# PrimaryLogger.net
KiCad netlist of a schematic drawn in EAGLE
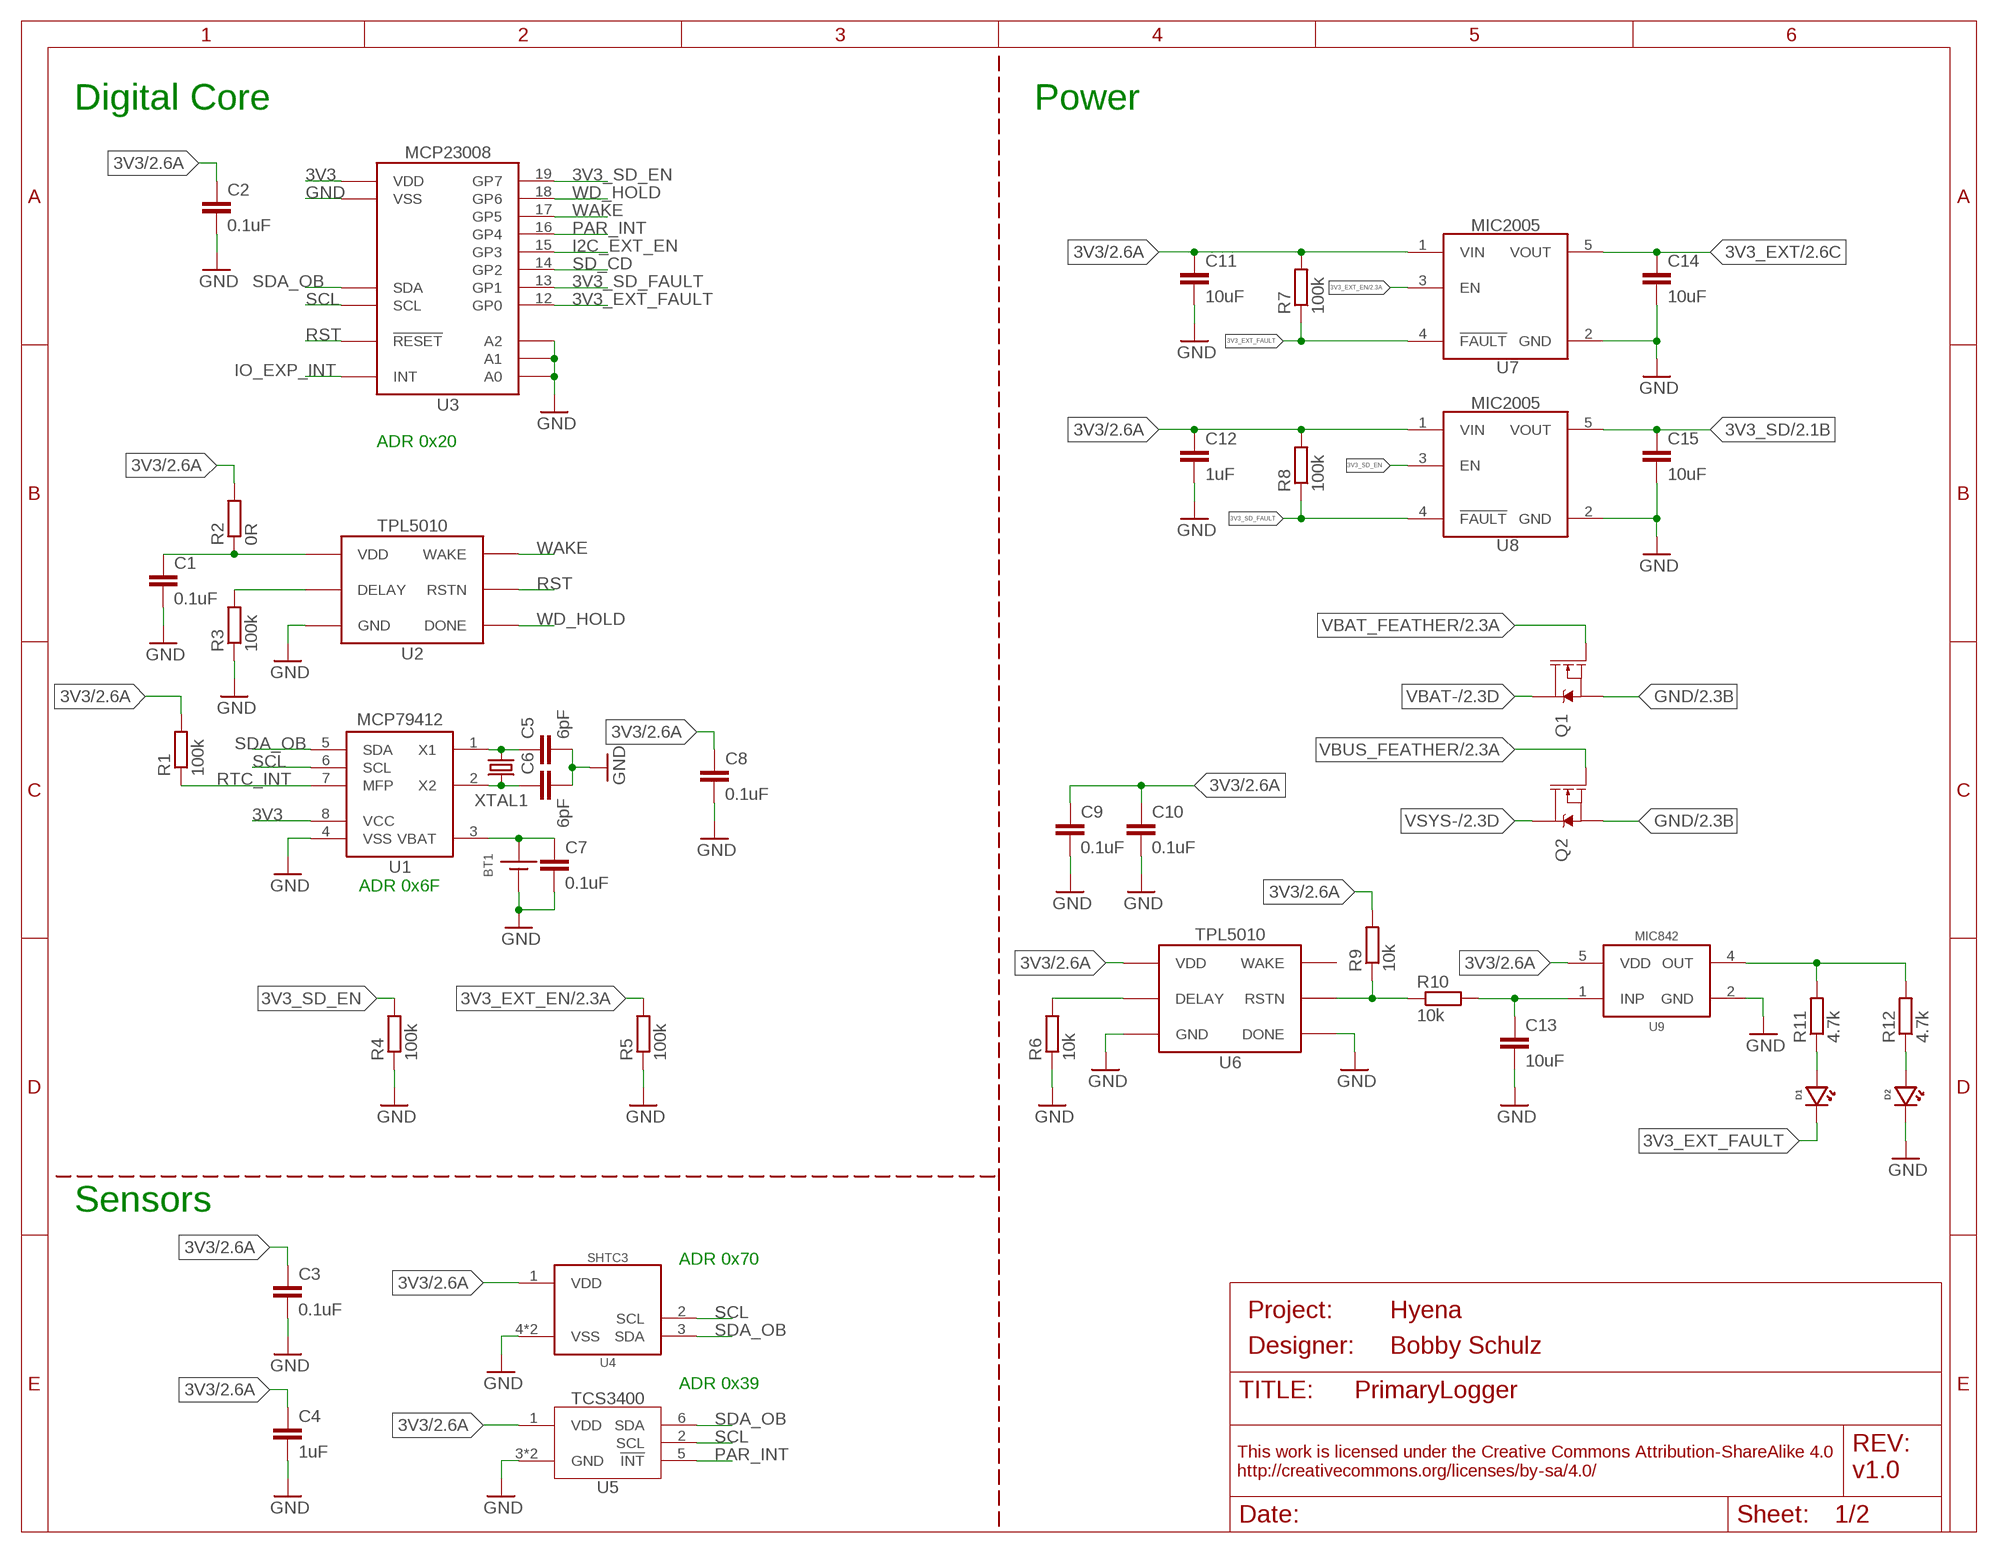
[diagram p0: schematic, sheet 1]
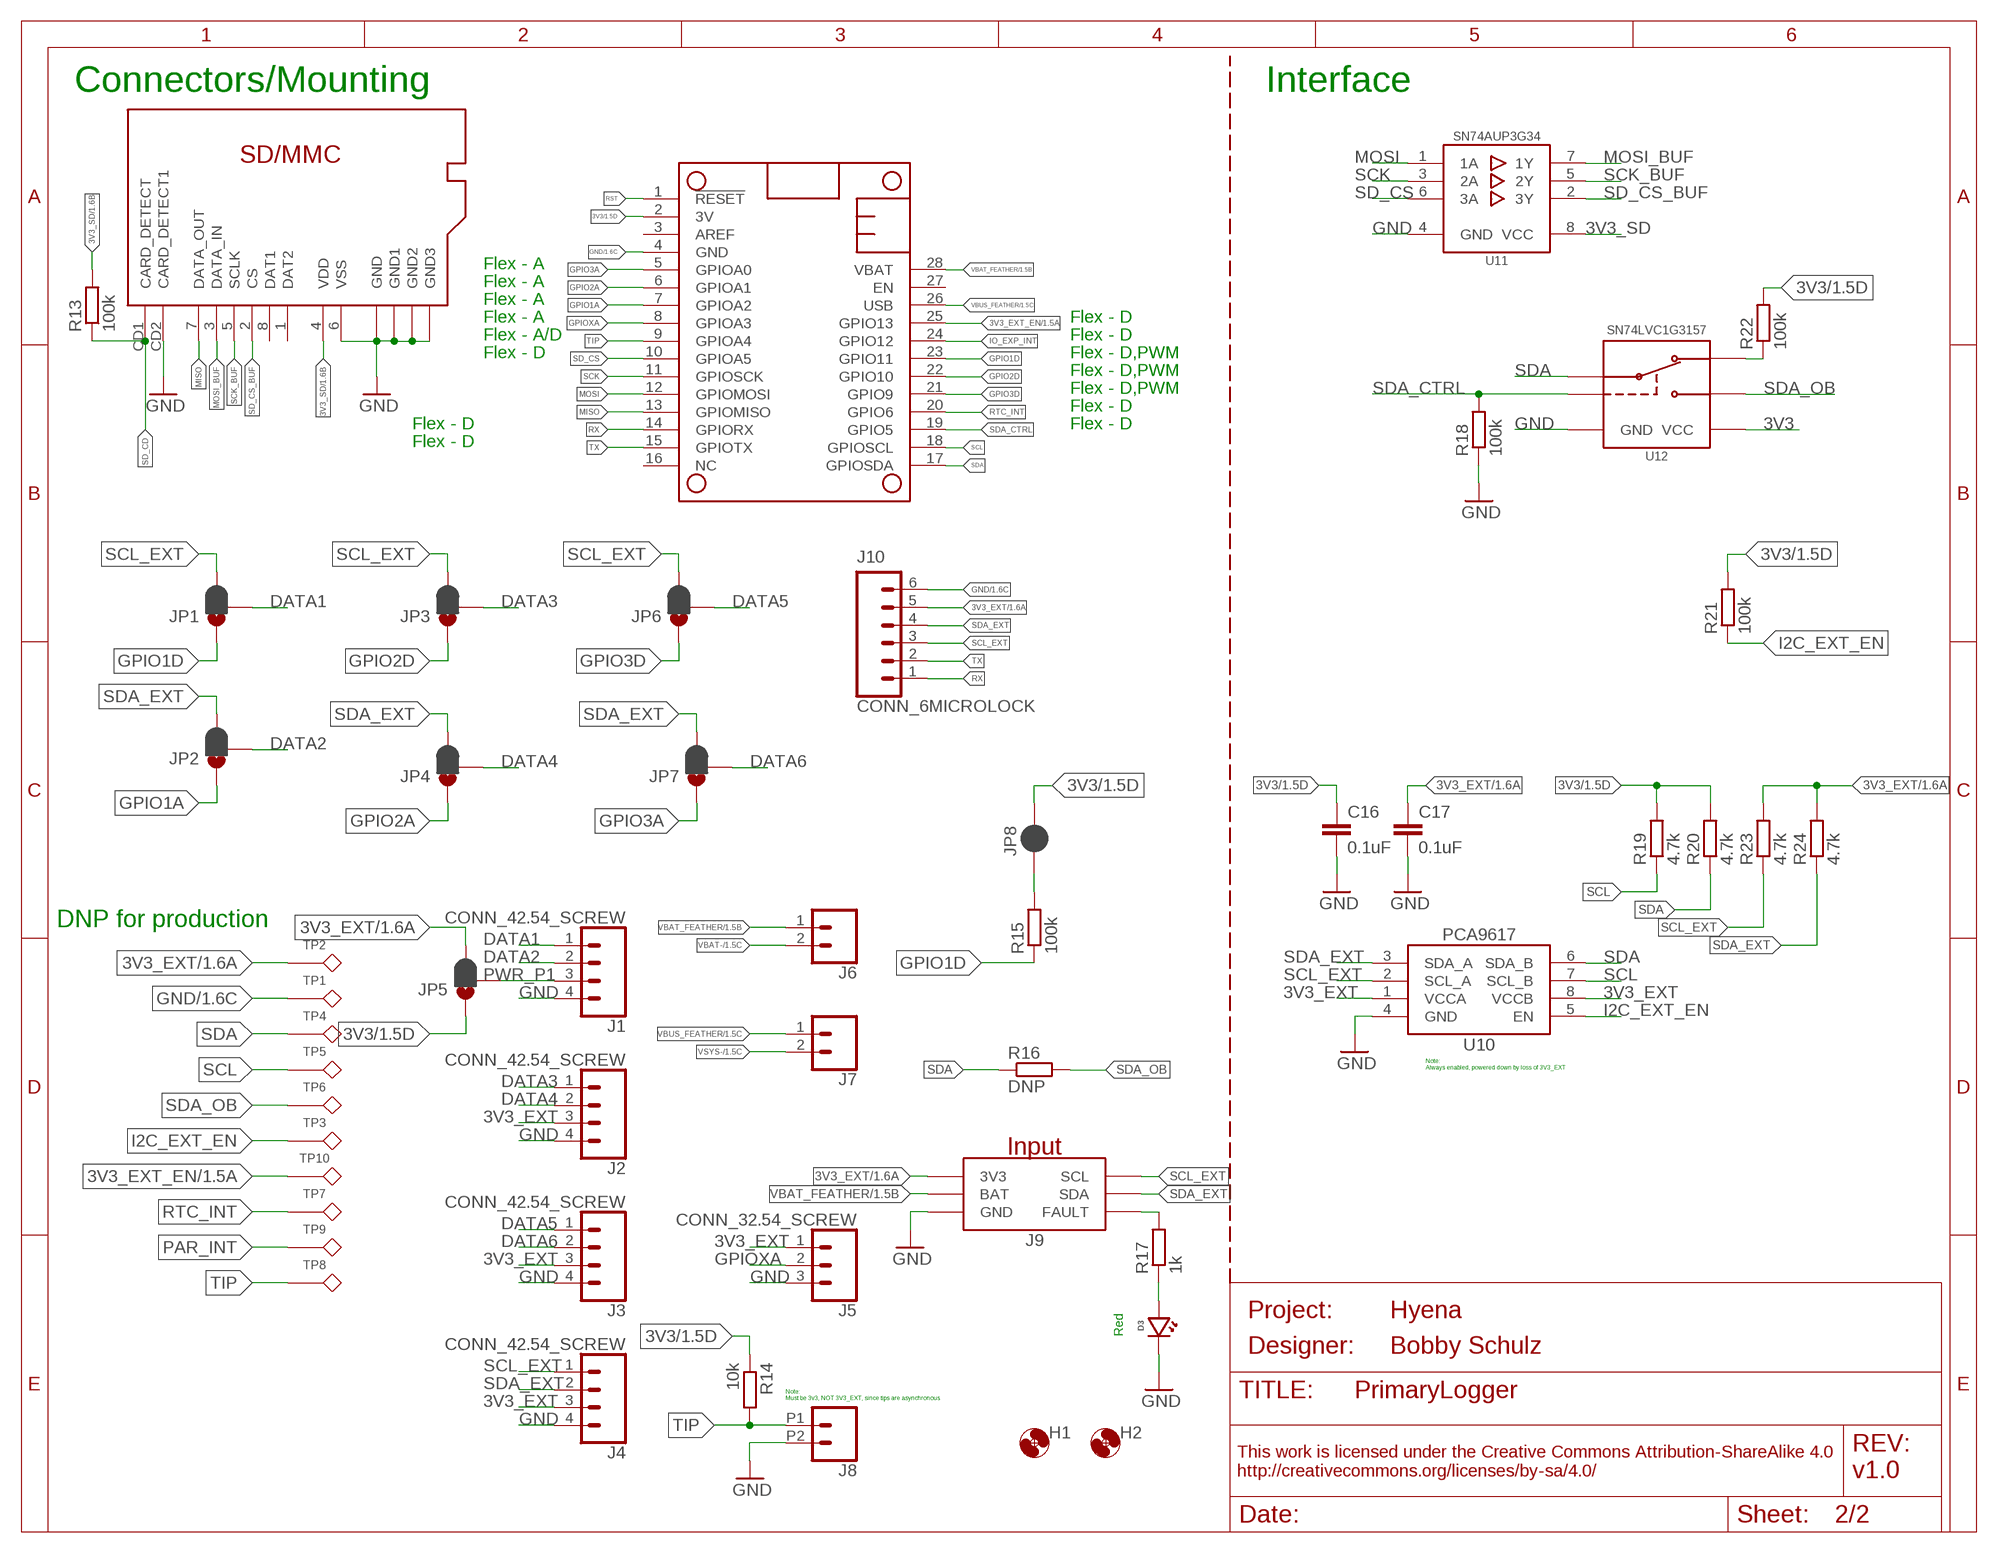
[diagram p1: schematic, sheet 2]

(export (version "E")
  (design (tool "Eeschema 10.0.6"))
  (components
    (comp (ref "BT1")
      (value "BATTERY_COIN12MM")
      (footprint "eagle-import:LINX_BAT-HLD-012-SMT")
      (fields (field (name "MF") "Linx") (field (name "MPN") "BAT-HLD-012-SMT"))
      (libsource (lib "eagle-import") (part "BATTERY_COIN12MM"))
    )
    (comp (ref "C1")
      (value "0.1uF")
      (footprint "eagle-import:C0603")
      (fields (field (name "MF") "Murata") (field (name "MPN") "GCM188R71E104KA57D"))
      (libsource (lib "eagle-import") (part "C-EUC06030.1UF"))
    )
    (comp (ref "C2")
      (value "0.1uF")
      (footprint "eagle-import:C0603")
      (fields (field (name "MF") "Murata") (field (name "MPN") "GCM188R71E104KA57D"))
      (libsource (lib "eagle-import") (part "C-EUC06030.1UF"))
    )
    (comp (ref "C3")
      (value "0.1uF")
      (footprint "eagle-import:C0603")
      (fields (field (name "MF") "Murata") (field (name "MPN") "GCM188R71E104KA57D"))
      (libsource (lib "eagle-import") (part "C-EUC06030.1UF"))
    )
    (comp (ref "C4")
      (value "1uF")
      (footprint "eagle-import:C0603")
      (fields (field (name "MF") "Yaiyo Yuden") (field (name "MPN") "EMK107BJ105KA-T"))
      (libsource (lib "eagle-import") (part "C-EUC06031UF"))
    )
    (comp (ref "C5")
      (value "6pF")
      (footprint "eagle-import:C0402")
      (fields (field (name "MF") "Murata") (field (name "MPN") "GJM1555C1H6R0CB01D"))
      (libsource (lib "eagle-import") (part "C-EUC04026PF"))
    )
    (comp (ref "C6")
      (value "6pF")
      (footprint "eagle-import:C0402")
      (fields (field (name "MF") "Murata") (field (name "MPN") "GJM1555C1H6R0CB01D"))
      (libsource (lib "eagle-import") (part "C-EUC04026PF"))
    )
    (comp (ref "C7")
      (value "0.1uF")
      (footprint "eagle-import:C0603")
      (fields (field (name "MF") "Murata") (field (name "MPN") "GCM188R71E104KA57D"))
      (libsource (lib "eagle-import") (part "C-EUC06030.1UF"))
    )
    (comp (ref "C8")
      (value "0.1uF")
      (footprint "eagle-import:C0603")
      (fields (field (name "MF") "Murata") (field (name "MPN") "GCM188R71E104KA57D"))
      (libsource (lib "eagle-import") (part "C-EUC06030.1UF"))
    )
    (comp (ref "C9")
      (value "0.1uF")
      (footprint "eagle-import:C0603")
      (fields (field (name "MF") "Murata") (field (name "MPN") "GCM188R71E104KA57D"))
      (libsource (lib "eagle-import") (part "C-EUC06030.1UF"))
    )
    (comp (ref "C10")
      (value "0.1uF")
      (footprint "eagle-import:C0603")
      (fields (field (name "MF") "Murata") (field (name "MPN") "GCM188R71E104KA57D"))
      (libsource (lib "eagle-import") (part "C-EUC06030.1UF"))
    )
    (comp (ref "C11")
      (value "10uF")
      (footprint "eagle-import:C0805")
      (fields (field (name "MF") "Murata") (field (name "MPN") "GRM21BR61C106KE15K"))
      (libsource (lib "eagle-import") (part "C-EUC080510UF"))
    )
    (comp (ref "C12")
      (value "1uF")
      (footprint "eagle-import:C0603")
      (fields (field (name "MF") "Yaiyo Yuden") (field (name "MPN") "EMK107BJ105KA-T"))
      (libsource (lib "eagle-import") (part "C-EUC06031UF"))
    )
    (comp (ref "C13")
      (value "10uF")
      (footprint "eagle-import:C0805")
      (fields (field (name "MF") "Murata") (field (name "MPN") "GRM21BR61C106KE15K"))
      (libsource (lib "eagle-import") (part "C-EUC080510UF"))
    )
    (comp (ref "C14")
      (value "10uF")
      (footprint "eagle-import:C0805")
      (fields (field (name "MF") "Murata") (field (name "MPN") "GRM21BR61C106KE15K"))
      (libsource (lib "eagle-import") (part "C-EUC080510UF"))
    )
    (comp (ref "C15")
      (value "10uF")
      (footprint "eagle-import:C0805")
      (fields (field (name "MF") "Murata") (field (name "MPN") "GRM21BR61C106KE15K"))
      (libsource (lib "eagle-import") (part "C-EUC080510UF"))
    )
    (comp (ref "D1")
      (value "LEDRED0603")
      (footprint "eagle-import:LED_0603")
      (fields (field (name "MF") "Wurth") (field (name "MPN") "150060RS75000"))
      (libsource (lib "eagle-import") (part "LED0603RED"))
    )
    (comp (ref "D2")
      (value "LEDGREEN0603")
      (footprint "eagle-import:LED_0603")
      (fields (field (name "MF") "Wurth") (field (name "MPN") "150060GS75000"))
      (libsource (lib "eagle-import") (part "LED0603GREEN"))
    )
    (comp (ref "Q1")
      (value "DMG3404")
      (footprint "eagle-import:SOT23-3")
      (fields (field (name "MF") "Diodes Incorporated") (field (name "MPN") "DMG3404L-7"))
      (libsource (lib "eagle-import") (part "MOSFET-NCH-DMG3404L"))
    )
    (comp (ref "Q2")
      (value "DMG3404")
      (footprint "eagle-import:SOT23-3")
      (fields (field (name "MF") "Diodes Incorporated") (field (name "MPN") "DMG3404L-7"))
      (libsource (lib "eagle-import") (part "MOSFET-NCH-DMG3404L"))
    )
    (comp (ref "R1")
      (value "100k")
      (footprint "eagle-import:R0603")
      (fields (field (name "MF") "Yageo") (field (name "MPN") "RC0603FR-07100KL"))
      (libsource (lib "eagle-import") (part "R-EU_R0603100K"))
    )
    (comp (ref "R2")
      (value "0R")
      (footprint "eagle-import:R0603")
      (fields
        (field (name "MF") "Yageo")
        (field (name "MPN") "AC0603JR-070RL")
        (field (name "VALUE_PART") "0")
      )
      (libsource (lib "eagle-import") (part "R-EU_R06030.0"))
    )
    (comp (ref "R3")
      (value "100k")
      (footprint "eagle-import:R0603")
      (fields (field (name "MF") "Yageo") (field (name "MPN") "RC0603FR-07100KL"))
      (libsource (lib "eagle-import") (part "R-EU_R0603100K"))
    )
    (comp (ref "R4")
      (value "100k")
      (footprint "eagle-import:R0603")
      (fields (field (name "MF") "Yageo") (field (name "MPN") "RC0603FR-07100KL"))
      (libsource (lib "eagle-import") (part "R-EU_R0603100K"))
    )
    (comp (ref "R5")
      (value "100k")
      (footprint "eagle-import:R0603")
      (fields (field (name "MF") "Yageo") (field (name "MPN") "RC0603FR-07100KL"))
      (libsource (lib "eagle-import") (part "R-EU_R0603100K"))
    )
    (comp (ref "R6")
      (value "10k")
      (footprint "eagle-import:R0603")
      (fields (field (name "MF") "Yageo") (field (name "MPN") "RC0603FR-0710KL"))
      (libsource (lib "eagle-import") (part "R-EU_R060310K"))
    )
    (comp (ref "R7")
      (value "100k")
      (footprint "eagle-import:R0603")
      (fields (field (name "MF") "Yageo") (field (name "MPN") "RC0603FR-07100KL"))
      (libsource (lib "eagle-import") (part "R-EU_R0603100K"))
    )
    (comp (ref "R8")
      (value "100k")
      (footprint "eagle-import:R0603")
      (fields (field (name "MF") "Yageo") (field (name "MPN") "RC0603FR-07100KL"))
      (libsource (lib "eagle-import") (part "R-EU_R0603100K"))
    )
    (comp (ref "R9")
      (value "10k")
      (footprint "eagle-import:R0603")
      (fields (field (name "MF") "Yageo") (field (name "MPN") "RC0603FR-0710KL"))
      (libsource (lib "eagle-import") (part "R-EU_R060310K"))
    )
    (comp (ref "R10")
      (value "10k")
      (footprint "eagle-import:R0603")
      (fields (field (name "MF") "Yageo") (field (name "MPN") "RC0603FR-0710KL"))
      (libsource (lib "eagle-import") (part "R-EU_R060310K"))
    )
    (comp (ref "R11")
      (value "4.7k")
      (footprint "eagle-import:R0603")
      (fields (field (name "MF") "Yageo") (field (name "MPN") "RC0603FR-074K7L"))
      (libsource (lib "eagle-import") (part "R-EU_R06034.7K"))
    )
    (comp (ref "R12")
      (value "4.7k")
      (footprint "eagle-import:R0603")
      (fields (field (name "MF") "Yageo") (field (name "MPN") "RC0603FR-074K7L"))
      (libsource (lib "eagle-import") (part "R-EU_R06034.7K"))
    )
    (comp (ref "U1")
      (value "MCP79412SOIC")
      (footprint "eagle-import:SO08")
      (fields
        (field (name "DISP") "MCP79412")
        (field (name "MF") "Microchip")
        (field (name "MPN") "MCP79412-I/SN")
      )
      (libsource (lib "eagle-import") (part "MCP794SOIC12"))
    )
    (comp (ref "U2")
      (value "TPL5010DDC")
      (footprint "eagle-import:DDC_R-PDSO-G6")
      (fields (field (name "MF") "TI") (field (name "MPN") "TPL5010DDCT"))
      (libsource (lib "eagle-import") (part "TPL5010DDC"))
    )
    (comp (ref "U3")
      (value "MCP23008SSOP")
      (footprint "eagle-import:SSOP20")
      (fields (field (name "MF") "Microchip") (field (name "MPN") "MCP23008T-E/SS"))
      (libsource (lib "eagle-import") (part "MCP23008SSOP"))
    )
    (comp (ref "U4")
      (value "SHTC3DFN")
      (footprint "eagle-import:DFN_4_2X2")
      (fields (field (name "DISP") "SHTC3") (field (name "MF") "Sensirion") (field (name "MPN") "SHTC3"))
      (libsource (lib "eagle-import") (part "SHTCDFN3"))
    )
    (comp (ref "U5")
      (value "TCS3400")
      (footprint "eagle-import:TCS3400")
      (fields (field (name "MF") "AMS") (field (name "MPN") "TCS34003FNM"))
      (libsource (lib "eagle-import") (part "TCS3400"))
    )
    (comp (ref "U6")
      (value "TPL5010DDC")
      (footprint "eagle-import:DDC_R-PDSO-G6")
      (fields (field (name "MF") "TI") (field (name "MPN") "TPL5010DDCT"))
      (libsource (lib "eagle-import") (part "TPL5010DDC"))
    )
    (comp (ref "U7")
      (value "MIC2005")
      (footprint "eagle-import:SOT23-5")
      (fields
        (field (name "DISP") "MIC2005")
        (field (name "MF") "Microchip")
        (field (name "MPN") "MIC2005A-1YM5-TR")
      )
      (libsource (lib "eagle-import") (part "MIC2005"))
    )
    (comp (ref "U8")
      (value "MIC2005")
      (footprint "eagle-import:SOT23-5")
      (fields
        (field (name "DISP") "MIC2005")
        (field (name "MF") "Microchip")
        (field (name "MPN") "MIC2005A-1YM5-TR")
      )
      (libsource (lib "eagle-import") (part "MIC2005"))
    )
    (comp (ref "U9")
      (value "MIC842L")
      (footprint "eagle-import:DCK_R-PDSO-G5")
      (fields (field (name "MF") "Microchip") (field (name "MPN") "MIC842LYC5-TR"))
      (libsource (lib "eagle-import") (part "MIC842L"))
    )
    (comp (ref "XTAL1")
      (value "CRYSTAL3.2X1.5")
      (footprint "eagle-import:CRYSTAL_3.2X1.5_2-SMD")
      (fields
        (field (name "DIGIKEY") "535-11937-1-ND")
        (field (name "MF") "ABS07-120-32.768KHZ-T")
        (field (name "MPN") "Abracon")
      )
      (libsource (lib "eagle-import") (part "CRYSTAL3.2X1.5"))
    )
    (comp (ref "C16")
      (value "0.1uF")
      (footprint "eagle-import:C0603")
      (fields (field (name "MF") "Murata") (field (name "MPN") "GCM188R71E104KA57D"))
      (libsource (lib "eagle-import") (part "C-EUC06030.1UF"))
    )
    (comp (ref "C17")
      (value "0.1uF")
      (footprint "eagle-import:C0603")
      (fields (field (name "MF") "Murata") (field (name "MPN") "GCM188R71E104KA57D"))
      (libsource (lib "eagle-import") (part "C-EUC06030.1UF"))
    )
    (comp (ref "D3")
      (value "LEDRED0603")
      (footprint "eagle-import:LED_0603")
      (fields (field (name "MF") "Wurth") (field (name "MPN") "150060RS75000"))
      (libsource (lib "eagle-import") (part "LED0603RED"))
    )
    (comp (ref "H1")
      (value "MOUNTING_HOLE2_NP")
      (footprint "eagle-import:2_56")
      (fields (field (name "MPN") "DNP"))
      (libsource (lib "eagle-import") (part "MOUNTING_HOLE2_NP"))
    )
    (comp (ref "H2")
      (value "MOUNTING_HOLE2_NP")
      (footprint "eagle-import:2_56")
      (fields (field (name "MPN") "DNP"))
      (libsource (lib "eagle-import") (part "MOUNTING_HOLE2_NP"))
    )
    (comp (ref "J1")
      (value "CONN_42.54_SCREW")
      (footprint "eagle-import:1X04_SCREW")
      (fields (field (name "MF") "On Shore") (field (name "MPN") "OSTVN04A150"))
      (libsource (lib "eagle-import") (part "CONN_42.54_SCREW"))
    )
    (comp (ref "J2")
      (value "CONN_42.54_SCREW")
      (footprint "eagle-import:1X04_SCREW")
      (fields (field (name "MF") "On Shore") (field (name "MPN") "OSTVN04A150"))
      (libsource (lib "eagle-import") (part "CONN_42.54_SCREW"))
    )
    (comp (ref "J3")
      (value "CONN_42.54_SCREW")
      (footprint "eagle-import:1X04_SCREW")
      (fields (field (name "MF") "On Shore") (field (name "MPN") "OSTVN04A150"))
      (libsource (lib "eagle-import") (part "CONN_42.54_SCREW"))
    )
    (comp (ref "J4")
      (value "CONN_42.54_SCREW")
      (footprint "eagle-import:1X04_SCREW")
      (fields (field (name "MF") "On Shore") (field (name "MPN") "OSTVN04A150"))
      (libsource (lib "eagle-import") (part "CONN_42.54_SCREW"))
    )
    (comp (ref "J5")
      (value "CONN_32.54_SCREW")
      (footprint "eagle-import:1X03_SCREW")
      (fields (field (name "MF") "On Shore") (field (name "MPN") "OSTVN03A150"))
      (libsource (lib "eagle-import") (part "CONN_32.54_SCREW"))
    )
    (comp (ref "J6")
      (value "CONN_023.5MM_ROUND")
      (footprint "eagle-import:SCREWTERMINAL-3.5MM-2_ROUND")
      (fields (field (name "MF") "OnShore") (field (name "MPN") "OSTTE020161"))
      (libsource (lib "eagle-import") (part "CONN_023.5MM_ROUND"))
    )
    (comp (ref "J7")
      (value "CONN_023.5MM_ROUND")
      (footprint "eagle-import:SCREWTERMINAL-3.5MM-2_ROUND")
      (fields (field (name "MF") "OnShore") (field (name "MPN") "OSTTE020161"))
      (libsource (lib "eagle-import") (part "CONN_023.5MM_ROUND"))
    )
    (comp (ref "J8")
      (value "CONN_022.54_SCREW_ROUND")
      (footprint "eagle-import:1X02_2.54_SCREWTERM_ROUND")
      (fields (field (name "MF") "OnShore") (field (name "MPN") "OSTVN02A150"))
      (libsource (lib "eagle-import") (part "CONN_022.54_SCREW_ROUND"))
    )
    (comp (ref "J9")
      (value "GEMS_POWER_PLUGINPUT")
      (footprint "eagle-import:2X3_MICROFIT_RT")
      (fields (field (name "DISP") "Input") (field (name "MF") "Molex") (field (name "MPN") "0430450600"))
      (libsource (lib "eagle-import") (part "GEMS_POWER_PLUGINPUT"))
    )
    (comp (ref "J10")
      (value "CONN_6MICROLOCK")
      (footprint "eagle-import:1X06_MICROLOCKPLUS")
      (fields (field (name "MF") "Molex") (field (name "MPN") "2059570671"))
      (libsource (lib "eagle-import") (part "CONN_6MICROLOCK"))
    )
    (comp (ref "JP1")
      (value "JUMPER-SMT_3_1-NC_PASTE_SILK")
      (footprint "eagle-import:SMT-JUMPER_3_1-NC_PASTE_SILK")
      (libsource (lib "eagle-import") (part "JUMPER-SMT_3_1-NC_PASTE_SILK"))
    )
    (comp (ref "JP2")
      (value "JUMPER-SMT_3_1-NC_PASTE_SILK")
      (footprint "eagle-import:SMT-JUMPER_3_1-NC_PASTE_SILK")
      (libsource (lib "eagle-import") (part "JUMPER-SMT_3_1-NC_PASTE_SILK"))
    )
    (comp (ref "JP3")
      (value "JUMPER-SMT_3_1-NC_PASTE_SILK")
      (footprint "eagle-import:SMT-JUMPER_3_1-NC_PASTE_SILK")
      (libsource (lib "eagle-import") (part "JUMPER-SMT_3_1-NC_PASTE_SILK"))
    )
    (comp (ref "JP4")
      (value "JUMPER-SMT_3_1-NC_PASTE_SILK")
      (footprint "eagle-import:SMT-JUMPER_3_1-NC_PASTE_SILK")
      (libsource (lib "eagle-import") (part "JUMPER-SMT_3_1-NC_PASTE_SILK"))
    )
    (comp (ref "JP5")
      (value "JUMPER-SMT_3_1-NC_PASTE_SILK")
      (footprint "eagle-import:SMT-JUMPER_3_1-NC_PASTE_SILK")
      (libsource (lib "eagle-import") (part "JUMPER-SMT_3_1-NC_PASTE_SILK"))
    )
    (comp (ref "JP6")
      (value "JUMPER-SMT_3_1-NC_PASTE_SILK")
      (footprint "eagle-import:SMT-JUMPER_3_1-NC_PASTE_SILK")
      (libsource (lib "eagle-import") (part "JUMPER-SMT_3_1-NC_PASTE_SILK"))
    )
    (comp (ref "JP7")
      (value "JUMPER-SMT_3_1-NC_PASTE_SILK")
      (footprint "eagle-import:SMT-JUMPER_3_1-NC_PASTE_SILK")
      (libsource (lib "eagle-import") (part "JUMPER-SMT_3_1-NC_PASTE_SILK"))
    )
    (comp (ref "JP8")
      (value "JUMPER-SMT_2_NC_PASTE_SILK")
      (footprint "eagle-import:SMT-JUMPER_2_NC_PASTE_SILK")
      (libsource (lib "eagle-import") (part "JUMPER-SMT_2_NC_PASTE_SILK"))
    )
    (comp (ref "MS1")
      (value "FEATHERWINGLAYOUT")
      (footprint "eagle-import:FEATHERWING_MIN")
      (libsource (lib "eagle-import") (part "FEATHERWINGLAYOUT"))
    )
    (comp (ref "R13")
      (value "100k")
      (footprint "eagle-import:R0603")
      (fields (field (name "MF") "Yageo") (field (name "MPN") "RC0603FR-07100KL"))
      (libsource (lib "eagle-import") (part "R-EU_R0603100K"))
    )
    (comp (ref "R14")
      (value "10k")
      (footprint "eagle-import:R0603")
      (fields (field (name "MF") "Yageo") (field (name "MPN") "RC0603FR-0710KL"))
      (libsource (lib "eagle-import") (part "R-EU_R060310K"))
    )
    (comp (ref "R15")
      (value "100k")
      (footprint "eagle-import:R0603")
      (fields (field (name "MF") "Yageo") (field (name "MPN") "RC0603FR-07100KL"))
      (libsource (lib "eagle-import") (part "R-EU_R0603100K"))
    )
    (comp (ref "R16")
      (value "DNP")
      (footprint "eagle-import:R0603")
      (fields
        (field (name "MF") "Yageo")
        (field (name "MPN") "AC0603JR-070RL")
        (field (name "VALUE_PART") "0")
      )
      (libsource (lib "eagle-import") (part "R-EU_R06030.0"))
    )
    (comp (ref "R17")
      (value "1k")
      (footprint "eagle-import:R0603")
      (fields (field (name "MF") "Yageo") (field (name "MPN") "AC0603FR-071KL"))
      (libsource (lib "eagle-import") (part "R-EU_R06031K"))
    )
    (comp (ref "R18")
      (value "100k")
      (footprint "eagle-import:R0603")
      (fields (field (name "MF") "Yageo") (field (name "MPN") "RC0603FR-07100KL"))
      (libsource (lib "eagle-import") (part "R-EU_R0603100K"))
    )
    (comp (ref "R19")
      (value "4.7k")
      (footprint "eagle-import:R0603")
      (fields (field (name "MF") "Yageo") (field (name "MPN") "RC0603FR-074K7L"))
      (libsource (lib "eagle-import") (part "R-EU_R06034.7K"))
    )
    (comp (ref "R20")
      (value "4.7k")
      (footprint "eagle-import:R0603")
      (fields (field (name "MF") "Yageo") (field (name "MPN") "RC0603FR-074K7L"))
      (libsource (lib "eagle-import") (part "R-EU_R06034.7K"))
    )
    (comp (ref "R21")
      (value "100k")
      (footprint "eagle-import:R0603")
      (fields (field (name "MF") "Yageo") (field (name "MPN") "RC0603FR-07100KL"))
      (libsource (lib "eagle-import") (part "R-EU_R0603100K"))
    )
    (comp (ref "R22")
      (value "100k")
      (footprint "eagle-import:R0603")
      (fields (field (name "MF") "Yageo") (field (name "MPN") "RC0603FR-07100KL"))
      (libsource (lib "eagle-import") (part "R-EU_R0603100K"))
    )
    (comp (ref "R23")
      (value "4.7k")
      (footprint "eagle-import:R0603")
      (fields (field (name "MF") "Yageo") (field (name "MPN") "RC0603FR-074K7L"))
      (libsource (lib "eagle-import") (part "R-EU_R06034.7K"))
    )
    (comp (ref "R24")
      (value "4.7k")
      (footprint "eagle-import:R0603")
      (fields (field (name "MF") "Yageo") (field (name "MPN") "RC0603FR-074K7L"))
      (libsource (lib "eagle-import") (part "R-EU_R06034.7K"))
    )
    (comp (ref "SD1")
      (value "MICRO_SD")
      (footprint "eagle-import:CUSTOM-PARTS_SD_MICRO")
      (fields (field (name "MF") "Amphenol") (field (name "MPN") "114-00841-68"))
      (libsource (lib "eagle-import") (part "MICRO_SD"))
    )
    (comp (ref "TP1")
      (value "TESTPOINTRCU")
      (footprint "eagle-import:TESTPOINT_0603")
      (fields (field (name "MF") "TE Connectivity") (field (name "MPN") "RCU-0C"))
      (libsource (lib "eagle-import") (part "TESTPOINTRCU"))
    )
    (comp (ref "TP2")
      (value "TESTPOINTRCU")
      (footprint "eagle-import:TESTPOINT_0603")
      (fields (field (name "MF") "TE Connectivity") (field (name "MPN") "RCU-0C"))
      (libsource (lib "eagle-import") (part "TESTPOINTRCU"))
    )
    (comp (ref "TP3")
      (value "TESTPOINTRCU")
      (footprint "eagle-import:TESTPOINT_0603")
      (fields (field (name "MF") "TE Connectivity") (field (name "MPN") "RCU-0C"))
      (libsource (lib "eagle-import") (part "TESTPOINTRCU"))
    )
    (comp (ref "TP4")
      (value "TESTPOINTRCU")
      (footprint "eagle-import:TESTPOINT_0603")
      (fields (field (name "MF") "TE Connectivity") (field (name "MPN") "RCU-0C"))
      (libsource (lib "eagle-import") (part "TESTPOINTRCU"))
    )
    (comp (ref "TP5")
      (value "TESTPOINTRCU")
      (footprint "eagle-import:TESTPOINT_0603")
      (fields (field (name "MF") "TE Connectivity") (field (name "MPN") "RCU-0C"))
      (libsource (lib "eagle-import") (part "TESTPOINTRCU"))
    )
    (comp (ref "TP6")
      (value "TESTPOINTRCU")
      (footprint "eagle-import:TESTPOINT_0603")
      (fields (field (name "MF") "TE Connectivity") (field (name "MPN") "RCU-0C"))
      (libsource (lib "eagle-import") (part "TESTPOINTRCU"))
    )
    (comp (ref "TP7")
      (value "TESTPOINTRCU")
      (footprint "eagle-import:TESTPOINT_0603")
      (fields (field (name "MF") "TE Connectivity") (field (name "MPN") "RCU-0C"))
      (libsource (lib "eagle-import") (part "TESTPOINTRCU"))
    )
    (comp (ref "TP8")
      (value "TESTPOINTRCU")
      (footprint "eagle-import:TESTPOINT_0603")
      (fields (field (name "MF") "TE Connectivity") (field (name "MPN") "RCU-0C"))
      (libsource (lib "eagle-import") (part "TESTPOINTRCU"))
    )
    (comp (ref "TP9")
      (value "TESTPOINTRCU")
      (footprint "eagle-import:TESTPOINT_0603")
      (fields (field (name "MF") "TE Connectivity") (field (name "MPN") "RCU-0C"))
      (libsource (lib "eagle-import") (part "TESTPOINTRCU"))
    )
    (comp (ref "TP10")
      (value "TESTPOINTRCU")
      (footprint "eagle-import:TESTPOINT_0603")
      (fields (field (name "MF") "TE Connectivity") (field (name "MPN") "RCU-0C"))
      (libsource (lib "eagle-import") (part "TESTPOINTRCU"))
    )
    (comp (ref "U10")
      (value "PCA9617")
      (footprint "eagle-import:TSSOP_8")
      (fields (field (name "MF") "NXP") (field (name "MPN") "PCA9617ADPJ"))
      (libsource (lib "eagle-import") (part "PCA9617"))
    )
    (comp (ref "U11")
      (value "SN74AUP3G34DCU")
      (footprint "eagle-import:DCU_(R-PDSO-G8)")
      (fields (field (name "MF") "TI") (field (name "MPN") "SN74AUP3G34DCUR"))
      (libsource (lib "eagle-import") (part "SN74AUP3G34DCU"))
    )
    (comp (ref "U12")
      (value "SN74LVC1G3157SC70")
      (footprint "eagle-import:DCK_R-PDSO-G6")
      (fields
        (field (name "DISP") "SN74LVC1G3157")
        (field (name "MF") "TI")
        (field (name "MPN") "SN74LVC1G3157DCKR")
      )
      (libsource (lib "eagle-import") (part "SN74LVC1G3157SC70"))
    )
  )
  (nets
    (net (code "1") (name "3V3") (class "Default")
      (node (ref "C10") (pin "1") (pinfunction "1_1") (pintype "passive"))
      (node (ref "C11") (pin "1") (pinfunction "1_1") (pintype "passive"))
      (node (ref "C12") (pin "1") (pinfunction "1_1") (pintype "passive"))
      (node (ref "C16") (pin "1") (pinfunction "1_1") (pintype "passive"))
      (node (ref "C2") (pin "1") (pinfunction "1_1") (pintype "passive"))
      (node (ref "C3") (pin "1") (pinfunction "1_1") (pintype "passive"))
      (node (ref "C4") (pin "1") (pinfunction "1_1") (pintype "passive"))
      (node (ref "C8") (pin "1") (pinfunction "1_1") (pintype "passive"))
      (node (ref "C9") (pin "1") (pinfunction "1_1") (pintype "passive"))
      (node (ref "JP5") (pin "1") (pinfunction "1_1") (pintype "passive"))
      (node (ref "JP8") (pin "2") (pinfunction "2_2") (pintype "passive"))
      (node (ref "MS1") (pin "2") (pinfunction "3V_2") (pintype "power_in"))
      (node (ref "R1") (pin "2") (pinfunction "2_2") (pintype "passive"))
      (node (ref "R14") (pin "1") (pinfunction "1_1") (pintype "passive"))
      (node (ref "R19") (pin "2") (pinfunction "2_2") (pintype "passive"))
      (node (ref "R2") (pin "2") (pinfunction "2_2") (pintype "passive"))
      (node (ref "R20") (pin "2") (pinfunction "2_2") (pintype "passive"))
      (node (ref "R21") (pin "2") (pinfunction "2_2") (pintype "passive"))
      (node (ref "R22") (pin "2") (pinfunction "2_2") (pintype "passive"))
      (node (ref "R7") (pin "2") (pinfunction "2_2") (pintype "passive"))
      (node (ref "R8") (pin "2") (pinfunction "2_2") (pintype "passive"))
      (node (ref "R9") (pin "2") (pinfunction "2_2") (pintype "passive"))
      (node (ref "U1") (pin "8") (pinfunction "VCC_8") (pintype "power_in"))
      (node (ref "U12") (pin "5") (pinfunction "VCC_5") (pintype "power_in"))
      (node (ref "U3") (pin "20") (pinfunction "VDD_20") (pintype "power_in"))
      (node (ref "U4") (pin "1") (pinfunction "VDD_1") (pintype "power_in"))
      (node (ref "U5") (pin "1") (pinfunction "VDD_1") (pintype "power_in"))
      (node (ref "U6") (pin "1") (pinfunction "VDD_1") (pintype "power_in"))
      (node (ref "U7") (pin "1") (pinfunction "VIN_1") (pintype "power_in"))
      (node (ref "U8") (pin "1") (pinfunction "VIN_1") (pintype "power_in"))
      (node (ref "U9") (pin "5") (pinfunction "VDD_5") (pintype "power_in"))
    )
    (net (code "2") (name "3V3_EXT") (class "Default")
      (node (ref "C14") (pin "1") (pinfunction "1_1") (pintype "passive"))
      (node (ref "C17") (pin "1") (pinfunction "1_1") (pintype "passive"))
      (node (ref "J10") (pin "5") (pinfunction "5_5") (pintype "passive"))
      (node (ref "J2") (pin "3") (pinfunction "3_3") (pintype "passive"))
      (node (ref "J3") (pin "3") (pinfunction "3_3") (pintype "passive"))
      (node (ref "J4") (pin "3") (pinfunction "3_3") (pintype "passive"))
      (node (ref "J5") (pin "1") (pinfunction "1_1") (pintype "passive"))
      (node (ref "J9") (pin "5") (pinfunction "3V3_5") (pintype "power_in"))
      (node (ref "JP5") (pin "3") (pinfunction "3_3") (pintype "passive"))
      (node (ref "R23") (pin "2") (pinfunction "2_2") (pintype "passive"))
      (node (ref "R24") (pin "2") (pinfunction "2_2") (pintype "passive"))
      (node (ref "TP2") (pin "1") (pinfunction "P$1_1") (pintype "bidirectional"))
      (node (ref "U10") (pin "1") (pinfunction "VCCA_1") (pintype "power_in"))
      (node (ref "U10") (pin "8") (pinfunction "VCCB_8") (pintype "power_in"))
      (node (ref "U7") (pin "5") (pinfunction "VOUT_5") (pintype "power_in"))
    )
    (net (code "3") (name "3V3_EXT_EN") (class "Default")
      (node (ref "MS1") (pin "25") (pinfunction "GPIO13_25") (pintype "bidirectional"))
      (node (ref "R5") (pin "2") (pinfunction "2_2") (pintype "passive"))
      (node (ref "TP10") (pin "1") (pinfunction "P$1_1") (pintype "bidirectional"))
      (node (ref "U7") (pin "3") (pinfunction "EN_3") (pintype "input"))
    )
    (net (code "4") (name "3V3_EXT_FAULT") (class "Default")
      (node (ref "D1") (pin "CATHODE") (pinfunction "CATHODE_CATHODE") (pintype "power_in"))
      (node (ref "R7") (pin "1") (pinfunction "1_1") (pintype "passive"))
      (node (ref "U3") (pin "12") (pinfunction "GP0_12") (pintype "bidirectional"))
      (node (ref "U7") (pin "4") (pinfunction "~{FAULT}_4") (pintype "output"))
    )
    (net (code "5") (name "3V3_SD") (class "Default")
      (node (ref "C15") (pin "1") (pinfunction "1_1") (pintype "passive"))
      (node (ref "R13") (pin "2") (pinfunction "2_2") (pintype "passive"))
      (node (ref "SD1") (pin "4") (pinfunction "VDD_4") (pintype "bidirectional"))
      (node (ref "U11") (pin "8") (pinfunction "VCC_8") (pintype "power_in"))
      (node (ref "U8") (pin "5") (pinfunction "VOUT_5") (pintype "power_in"))
    )
    (net (code "6") (name "3V3_SD_EN") (class "Default")
      (node (ref "R4") (pin "2") (pinfunction "2_2") (pintype "passive"))
      (node (ref "U3") (pin "19") (pinfunction "GP7_19") (pintype "bidirectional"))
      (node (ref "U8") (pin "3") (pinfunction "EN_3") (pintype "input"))
    )
    (net (code "7") (name "3V3_SD_FAULT") (class "Default")
      (node (ref "R8") (pin "1") (pinfunction "1_1") (pintype "passive"))
      (node (ref "U3") (pin "13") (pinfunction "GP1_13") (pintype "bidirectional"))
      (node (ref "U8") (pin "4") (pinfunction "~{FAULT}_4") (pintype "output"))
    )
    (net (code "8") (name "DATA1") (class "Default")
      (node (ref "J1") (pin "1") (pinfunction "1_1") (pintype "passive"))
      (node (ref "JP1") (pin "2") (pinfunction "2_2") (pintype "passive"))
    )
    (net (code "9") (name "DATA2") (class "Default")
      (node (ref "J1") (pin "2") (pinfunction "2_2") (pintype "passive"))
      (node (ref "JP2") (pin "2") (pinfunction "2_2") (pintype "passive"))
    )
    (net (code "10") (name "DATA3") (class "Default")
      (node (ref "J2") (pin "1") (pinfunction "1_1") (pintype "passive"))
      (node (ref "JP3") (pin "2") (pinfunction "2_2") (pintype "passive"))
    )
    (net (code "11") (name "DATA4") (class "Default")
      (node (ref "J2") (pin "2") (pinfunction "2_2") (pintype "passive"))
      (node (ref "JP4") (pin "2") (pinfunction "2_2") (pintype "passive"))
    )
    (net (code "12") (name "DATA5") (class "Default")
      (node (ref "J3") (pin "1") (pinfunction "1_1") (pintype "passive"))
      (node (ref "JP6") (pin "2") (pinfunction "2_2") (pintype "passive"))
    )
    (net (code "13") (name "DATA6") (class "Default")
      (node (ref "J3") (pin "2") (pinfunction "2_2") (pintype "passive"))
      (node (ref "JP7") (pin "2") (pinfunction "2_2") (pintype "passive"))
    )
    (net (code "14") (name "GND") (class "Default")
      (node (ref "BT1") (pin "GND") (pinfunction "-_GND") (pintype "power_in"))
      (node (ref "C1") (pin "2") (pinfunction "2_2") (pintype "passive"))
      (node (ref "C10") (pin "2") (pinfunction "2_2") (pintype "passive"))
      (node (ref "C11") (pin "2") (pinfunction "2_2") (pintype "passive"))
      (node (ref "C12") (pin "2") (pinfunction "2_2") (pintype "passive"))
      (node (ref "C13") (pin "2") (pinfunction "2_2") (pintype "passive"))
      (node (ref "C14") (pin "2") (pinfunction "2_2") (pintype "passive"))
      (node (ref "C15") (pin "2") (pinfunction "2_2") (pintype "passive"))
      (node (ref "C16") (pin "2") (pinfunction "2_2") (pintype "passive"))
      (node (ref "C17") (pin "2") (pinfunction "2_2") (pintype "passive"))
      (node (ref "C2") (pin "2") (pinfunction "2_2") (pintype "passive"))
      (node (ref "C3") (pin "2") (pinfunction "2_2") (pintype "passive"))
      (node (ref "C4") (pin "2") (pinfunction "2_2") (pintype "passive"))
      (node (ref "C5") (pin "2") (pinfunction "2_2") (pintype "passive"))
      (node (ref "C6") (pin "2") (pinfunction "2_2") (pintype "passive"))
      (node (ref "C7") (pin "2") (pinfunction "2_2") (pintype "passive"))
      (node (ref "C8") (pin "2") (pinfunction "2_2") (pintype "passive"))
      (node (ref "C9") (pin "2") (pinfunction "2_2") (pintype "passive"))
      (node (ref "D2") (pin "CATHODE") (pinfunction "CATHODE_CATHODE") (pintype "power_in"))
      (node (ref "D3") (pin "CATHODE") (pinfunction "CATHODE_CATHODE") (pintype "power_in"))
      (node (ref "J1") (pin "4") (pinfunction "4_4") (pintype "passive"))
      (node (ref "J10") (pin "6") (pinfunction "6_6") (pintype "passive"))
      (node (ref "J2") (pin "4") (pinfunction "4_4") (pintype "passive"))
      (node (ref "J3") (pin "4") (pinfunction "4_4") (pintype "passive"))
      (node (ref "J4") (pin "4") (pinfunction "4_4") (pintype "passive"))
      (node (ref "J5") (pin "3") (pinfunction "3_3") (pintype "passive"))
      (node (ref "J8") (pin "P2") (pinfunction "2_P2") (pintype "passive"))
      (node (ref "J9") (pin "2") (pinfunction "GND_2") (pintype "power_in"))
      (node (ref "MS1") (pin "4") (pinfunction "GND_4") (pintype "power_in"))
      (node (ref "Q1") (pin "2") (pinfunction "S_2") (pintype "bidirectional"))
      (node (ref "Q2") (pin "2") (pinfunction "S_2") (pintype "bidirectional"))
      (node (ref "R18") (pin "1") (pinfunction "1_1") (pintype "passive"))
      (node (ref "R3") (pin "1") (pinfunction "1_1") (pintype "passive"))
      (node (ref "R4") (pin "1") (pinfunction "1_1") (pintype "passive"))
      (node (ref "R5") (pin "1") (pinfunction "1_1") (pintype "passive"))
      (node (ref "R6") (pin "1") (pinfunction "1_1") (pintype "passive"))
      (node (ref "SD1") (pin "6") (pinfunction "VSS_6") (pintype "bidirectional"))
      (node (ref "SD1") (pin "CD2") (pinfunction "CARD_DETECT1_CD2") (pintype "bidirectional"))
      (node (ref "SD1") (pin "GND@1") (pinfunction "GND_GND@1") (pintype "bidirectional"))
      (node (ref "SD1") (pin "GND@2") (pinfunction "GND1_GND@2") (pintype "bidirectional"))
      (node (ref "SD1") (pin "GND@3") (pinfunction "GND2_GND@3") (pintype "bidirectional"))
      (node (ref "SD1") (pin "GND@5") (pinfunction "GND3_GND@5") (pintype "bidirectional"))
      (node (ref "TP1") (pin "1") (pinfunction "P$1_1") (pintype "bidirectional"))
      (node (ref "U1") (pin "4") (pinfunction "VSS_4") (pintype "power_in"))
      (node (ref "U10") (pin "4") (pinfunction "GND_4") (pintype "power_in"))
      (node (ref "U11") (pin "4") (pinfunction "GND_4") (pintype "power_in"))
      (node (ref "U12") (pin "2") (pinfunction "GND_2") (pintype "power_in"))
      (node (ref "U2") (pin "2") (pinfunction "GND_2") (pintype "power_in"))
      (node (ref "U3") (pin "3") (pinfunction "A2_3") (pintype "input"))
      (node (ref "U3") (pin "4") (pinfunction "A1_4") (pintype "input"))
      (node (ref "U3") (pin "5") (pinfunction "A0_5") (pintype "input"))
      (node (ref "U3") (pin "9") (pinfunction "VSS_9") (pintype "power_in"))
      (node (ref "U4") (pin "4") (pinfunction "VSS_4") (pintype "power_in"))
      (node (ref "U4") (pin "EP") (pinfunction "VSS_EP") (pintype "power_in"))
      (node (ref "U5") (pin "3") (pinfunction "GND_3") (pintype "power_in"))
      (node (ref "U5") (pin "4") (pinfunction "GND_4") (pintype "power_in"))
      (node (ref "U6") (pin "2") (pinfunction "GND_2") (pintype "power_in"))
      (node (ref "U6") (pin "4") (pinfunction "DONE_4") (pintype "input"))
      (node (ref "U7") (pin "2") (pinfunction "GND_2") (pintype "power_in"))
      (node (ref "U8") (pin "2") (pinfunction "GND_2") (pintype "power_in"))
      (node (ref "U9") (pin "2") (pinfunction "GND_2") (pintype "power_in"))
    )
    (net (code "15") (name "GPIO1A") (class "Default")
      (node (ref "JP2") (pin "1") (pinfunction "1_1") (pintype "passive"))
      (node (ref "MS1") (pin "7") (pinfunction "GPIOA2_7") (pintype "bidirectional"))
    )
    (net (code "16") (name "GPIO1D") (class "Default")
      (node (ref "JP1") (pin "1") (pinfunction "1_1") (pintype "passive"))
      (node (ref "MS1") (pin "23") (pinfunction "GPIO11_23") (pintype "bidirectional"))
      (node (ref "R15") (pin "1") (pinfunction "1_1") (pintype "passive"))
    )
    (net (code "17") (name "GPIO2A") (class "Default")
      (node (ref "JP4") (pin "1") (pinfunction "1_1") (pintype "passive"))
      (node (ref "MS1") (pin "6") (pinfunction "GPIOA1_6") (pintype "bidirectional"))
    )
    (net (code "18") (name "GPIO2D") (class "Default")
      (node (ref "JP3") (pin "1") (pinfunction "1_1") (pintype "passive"))
      (node (ref "MS1") (pin "22") (pinfunction "GPIO10_22") (pintype "bidirectional"))
    )
    (net (code "19") (name "GPIO3A") (class "Default")
      (node (ref "JP7") (pin "1") (pinfunction "1_1") (pintype "passive"))
      (node (ref "MS1") (pin "5") (pinfunction "GPIOA0_5") (pintype "bidirectional"))
    )
    (net (code "20") (name "GPIO3D") (class "Default")
      (node (ref "JP6") (pin "1") (pinfunction "1_1") (pintype "passive"))
      (node (ref "MS1") (pin "21") (pinfunction "GPIO9_21") (pintype "bidirectional"))
    )
    (net (code "21") (name "GPIOXA") (class "Default")
      (node (ref "J5") (pin "2") (pinfunction "2_2") (pintype "passive"))
      (node (ref "MS1") (pin "8") (pinfunction "GPIOA3_8") (pintype "bidirectional"))
    )
    (net (code "22") (name "I2C_EXT_EN") (class "Default")
      (node (ref "R21") (pin "1") (pinfunction "1_1") (pintype "passive"))
      (node (ref "TP3") (pin "1") (pinfunction "P$1_1") (pintype "bidirectional"))
      (node (ref "U10") (pin "5") (pinfunction "EN_5") (pintype "open_collector"))
      (node (ref "U3") (pin "15") (pinfunction "GP3_15") (pintype "bidirectional"))
    )
    (net (code "23") (name "IO_EXP_INT") (class "Default")
      (node (ref "MS1") (pin "24") (pinfunction "GPIO12_24") (pintype "bidirectional"))
      (node (ref "U3") (pin "8") (pinfunction "INT_8") (pintype "output"))
    )
    (net (code "24") (name "MISO") (class "Default")
      (node (ref "MS1") (pin "13") (pinfunction "GPIOMISO_13") (pintype "bidirectional"))
      (node (ref "SD1") (pin "7") (pinfunction "DATA_OUT_7") (pintype "bidirectional"))
    )
    (net (code "25") (name "MOSI") (class "Default")
      (node (ref "MS1") (pin "12") (pinfunction "GPIOMOSI_12") (pintype "bidirectional"))
      (node (ref "U11") (pin "1") (pinfunction "1A_1") (pintype "input"))
    )
    (net (code "26") (name "MOSI_BUF") (class "Default")
      (node (ref "SD1") (pin "3") (pinfunction "DATA_IN_3") (pintype "bidirectional"))
      (node (ref "U11") (pin "7") (pinfunction "1Y_7") (pintype "output"))
    )
    (net (code "27") (name "Net-(D1-PadANODE)") (class "Default")
      (node (ref "D1") (pin "ANODE") (pinfunction "ANODE_ANODE") (pintype "power_in"))
      (node (ref "R11") (pin "1") (pinfunction "1_1") (pintype "passive"))
    )
    (net (code "28") (name "Net-(D2-PadANODE)") (class "Default")
      (node (ref "D2") (pin "ANODE") (pinfunction "ANODE_ANODE") (pintype "power_in"))
      (node (ref "R12") (pin "1") (pinfunction "1_1") (pintype "passive"))
    )
    (net (code "29") (name "Net-(D3-PadANODE)") (class "Default")
      (node (ref "D3") (pin "ANODE") (pinfunction "ANODE_ANODE") (pintype "power_in"))
      (node (ref "R17") (pin "1") (pinfunction "1_1") (pintype "passive"))
    )
    (net (code "30") (name "Net-(J9-FAULT)") (class "Default")
      (node (ref "J9") (pin "3") (pinfunction "FAULT_3") (pintype "bidirectional"))
      (node (ref "R17") (pin "2") (pinfunction "2_2") (pintype "passive"))
    )
    (net (code "31") (name "Net-(JP8-Pad1)") (class "Default")
      (node (ref "JP8") (pin "1") (pinfunction "1_1") (pintype "passive"))
      (node (ref "R15") (pin "2") (pinfunction "2_2") (pintype "passive"))
    )
    (net (code "32") (name "Net-(U1-VBAT)") (class "Default")
      (node (ref "BT1") (pin "POWER0") (pinfunction "+_POWER0") (pintype "power_in"))
      (node (ref "BT1") (pin "POWER1") (pinfunction "+_POWER1") (pintype "power_in"))
      (node (ref "C7") (pin "1") (pinfunction "1_1") (pintype "passive"))
      (node (ref "U1") (pin "3") (pinfunction "VBAT_3") (pintype "power_in"))
    )
    (net (code "33") (name "Net-(U1-X1)") (class "Default")
      (node (ref "C5") (pin "1") (pinfunction "1_1") (pintype "passive"))
      (node (ref "U1") (pin "1") (pinfunction "X1_1") (pintype "passive"))
      (node (ref "XTAL1") (pin "P$1") (pinfunction "1_P$1") (pintype "passive"))
    )
    (net (code "34") (name "Net-(U1-X2)") (class "Default")
      (node (ref "C6") (pin "1") (pinfunction "1_1") (pintype "passive"))
      (node (ref "U1") (pin "2") (pinfunction "X2_2") (pintype "passive"))
      (node (ref "XTAL1") (pin "P$2") (pinfunction "2_P$2") (pintype "passive"))
    )
    (net (code "35") (name "Net-(U2-DELAY)") (class "Default")
      (node (ref "R3") (pin "2") (pinfunction "2_2") (pintype "passive"))
      (node (ref "U2") (pin "3") (pinfunction "DELAY_3") (pintype "input"))
    )
    (net (code "36") (name "Net-(U2-VDD)") (class "Default")
      (node (ref "C1") (pin "1") (pinfunction "1_1") (pintype "passive"))
      (node (ref "R2") (pin "1") (pinfunction "1_1") (pintype "passive"))
      (node (ref "U2") (pin "1") (pinfunction "VDD_1") (pintype "power_in"))
    )
    (net (code "37") (name "Net-(U6-DELAY)") (class "Default")
      (node (ref "R6") (pin "2") (pinfunction "2_2") (pintype "passive"))
      (node (ref "U6") (pin "3") (pinfunction "DELAY_3") (pintype "input"))
    )
    (net (code "38") (name "Net-(U6-RSTN)") (class "Default")
      (node (ref "R10") (pin "1") (pinfunction "1_1") (pintype "passive"))
      (node (ref "R9") (pin "1") (pinfunction "1_1") (pintype "passive"))
      (node (ref "U6") (pin "6") (pinfunction "RSTN_6") (pintype "output"))
    )
    (net (code "39") (name "Net-(U9-INP)") (class "Default")
      (node (ref "C13") (pin "1") (pinfunction "1_1") (pintype "passive"))
      (node (ref "R10") (pin "2") (pinfunction "2_2") (pintype "passive"))
      (node (ref "U9") (pin "1") (pinfunction "INP_1") (pintype "input"))
    )
    (net (code "40") (name "Net-(U9-OUT)") (class "Default")
      (node (ref "R11") (pin "2") (pinfunction "2_2") (pintype "passive"))
      (node (ref "R12") (pin "2") (pinfunction "2_2") (pintype "passive"))
      (node (ref "U9") (pin "4") (pinfunction "OUT_4") (pintype "output"))
    )
    (net (code "41") (name "Net-(U12-B1)") (class "Default")
      (node (ref "R22") (pin "1") (pinfunction "1_1") (pintype "passive"))
      (node (ref "U12") (pin "3") (pinfunction "B1_3") (pintype "bidirectional"))
    )
    (net (code "42") (name "PAR_INT") (class "Default")
      (node (ref "TP9") (pin "1") (pinfunction "P$1_1") (pintype "bidirectional"))
      (node (ref "U3") (pin "16") (pinfunction "GP4_16") (pintype "bidirectional"))
      (node (ref "U5") (pin "5") (pinfunction "~{INT}_5") (pintype "output"))
    )
    (net (code "43") (name "PWR_P1") (class "Default")
      (node (ref "J1") (pin "3") (pinfunction "3_3") (pintype "passive"))
      (node (ref "JP5") (pin "2") (pinfunction "2_2") (pintype "passive"))
    )
    (net (code "44") (name "RST") (class "Default")
      (node (ref "MS1") (pin "1") (pinfunction "~{RESET}_1") (pintype "input"))
      (node (ref "U2") (pin "6") (pinfunction "RSTN_6") (pintype "output"))
      (node (ref "U3") (pin "6") (pinfunction "~{RESET}_6") (pintype "input"))
    )
    (net (code "45") (name "RTC_INT") (class "Default")
      (node (ref "MS1") (pin "20") (pinfunction "GPIO6_20") (pintype "bidirectional"))
      (node (ref "R1") (pin "1") (pinfunction "1_1") (pintype "passive"))
      (node (ref "TP7") (pin "1") (pinfunction "P$1_1") (pintype "bidirectional"))
      (node (ref "U1") (pin "7") (pinfunction "MFP_7") (pintype "bidirectional"))
    )
    (net (code "46") (name "RX") (class "Default")
      (node (ref "J10") (pin "1") (pinfunction "1_1") (pintype "passive"))
      (node (ref "MS1") (pin "14") (pinfunction "GPIORX_14") (pintype "bidirectional"))
    )
    (net (code "47") (name "SCK") (class "Default")
      (node (ref "MS1") (pin "11") (pinfunction "GPIOSCK_11") (pintype "bidirectional"))
      (node (ref "U11") (pin "3") (pinfunction "2A_3") (pintype "input"))
    )
    (net (code "48") (name "SCK_BUF") (class "Default")
      (node (ref "SD1") (pin "5") (pinfunction "SCLK_5") (pintype "bidirectional"))
      (node (ref "U11") (pin "5") (pinfunction "2Y_5") (pintype "output"))
    )
    (net (code "49") (name "SCL") (class "Default")
      (node (ref "MS1") (pin "18") (pinfunction "GPIOSCL_18") (pintype "bidirectional"))
      (node (ref "R19") (pin "1") (pinfunction "1_1") (pintype "passive"))
      (node (ref "TP5") (pin "1") (pinfunction "P$1_1") (pintype "bidirectional"))
      (node (ref "U1") (pin "6") (pinfunction "SCL_6") (pintype "input"))
      (node (ref "U10") (pin "7") (pinfunction "SCL_B_7") (pintype "open_collector"))
      (node (ref "U3") (pin "1") (pinfunction "SCL_1") (pintype "input"))
      (node (ref "U4") (pin "2") (pinfunction "SCL_2") (pintype "input"))
      (node (ref "U5") (pin "2") (pinfunction "SCL_2") (pintype "input"))
    )
    (net (code "50") (name "SCL_EXT") (class "Default")
      (node (ref "J10") (pin "3") (pinfunction "3_3") (pintype "passive"))
      (node (ref "J4") (pin "1") (pinfunction "1_1") (pintype "passive"))
      (node (ref "J9") (pin "6") (pinfunction "SCL_6") (pintype "bidirectional"))
      (node (ref "JP1") (pin "3") (pinfunction "3_3") (pintype "passive"))
      (node (ref "JP3") (pin "3") (pinfunction "3_3") (pintype "passive"))
      (node (ref "JP6") (pin "3") (pinfunction "3_3") (pintype "passive"))
      (node (ref "R23") (pin "1") (pinfunction "1_1") (pintype "passive"))
      (node (ref "U10") (pin "2") (pinfunction "SCL_A_2") (pintype "open_collector"))
    )
    (net (code "51") (name "SDA") (class "Default")
      (node (ref "MS1") (pin "17") (pinfunction "GPIOSDA_17") (pintype "bidirectional"))
      (node (ref "R16") (pin "1") (pinfunction "1_1") (pintype "passive"))
      (node (ref "R20") (pin "1") (pinfunction "1_1") (pintype "passive"))
      (node (ref "TP4") (pin "1") (pinfunction "P$1_1") (pintype "bidirectional"))
      (node (ref "U10") (pin "6") (pinfunction "SDA_B_6") (pintype "open_collector"))
      (node (ref "U12") (pin "4") (pinfunction "A_4") (pintype "bidirectional"))
    )
    (net (code "52") (name "SDA_CTRL") (class "Default")
      (node (ref "MS1") (pin "19") (pinfunction "GPIO5_19") (pintype "bidirectional"))
      (node (ref "R18") (pin "2") (pinfunction "2_2") (pintype "passive"))
      (node (ref "U12") (pin "6") (pinfunction "S_6") (pintype "input"))
    )
    (net (code "53") (name "SDA_EXT") (class "Default")
      (node (ref "J10") (pin "4") (pinfunction "4_4") (pintype "passive"))
      (node (ref "J4") (pin "2") (pinfunction "2_2") (pintype "passive"))
      (node (ref "J9") (pin "4") (pinfunction "SDA_4") (pintype "bidirectional"))
      (node (ref "JP2") (pin "3") (pinfunction "3_3") (pintype "passive"))
      (node (ref "JP4") (pin "3") (pinfunction "3_3") (pintype "passive"))
      (node (ref "JP7") (pin "3") (pinfunction "3_3") (pintype "passive"))
      (node (ref "R24") (pin "1") (pinfunction "1_1") (pintype "passive"))
      (node (ref "U10") (pin "3") (pinfunction "SDA_A_3") (pintype "open_collector"))
    )
    (net (code "54") (name "SDA_OB") (class "Default")
      (node (ref "R16") (pin "2") (pinfunction "2_2") (pintype "passive"))
      (node (ref "TP6") (pin "1") (pinfunction "P$1_1") (pintype "bidirectional"))
      (node (ref "U1") (pin "5") (pinfunction "SDA_5") (pintype "bidirectional"))
      (node (ref "U12") (pin "1") (pinfunction "B2_1") (pintype "bidirectional"))
      (node (ref "U3") (pin "2") (pinfunction "SDA_2") (pintype "bidirectional"))
      (node (ref "U4") (pin "3") (pinfunction "SDA_3") (pintype "bidirectional"))
      (node (ref "U5") (pin "6") (pinfunction "SDA_6") (pintype "bidirectional"))
    )
    (net (code "55") (name "SD_CD") (class "Default")
      (node (ref "R13") (pin "1") (pinfunction "1_1") (pintype "passive"))
      (node (ref "SD1") (pin "CD1") (pinfunction "CARD_DETECT_CD1") (pintype "bidirectional"))
      (node (ref "U3") (pin "14") (pinfunction "GP2_14") (pintype "bidirectional"))
    )
    (net (code "56") (name "SD_CS") (class "Default")
      (node (ref "MS1") (pin "10") (pinfunction "GPIOA5_10") (pintype "bidirectional"))
      (node (ref "U11") (pin "6") (pinfunction "3A_6") (pintype "input"))
    )
    (net (code "57") (name "SD_CS_BUF") (class "Default")
      (node (ref "SD1") (pin "2") (pinfunction "CS_2") (pintype "bidirectional"))
      (node (ref "U11") (pin "2") (pinfunction "3Y_2") (pintype "output"))
    )
    (net (code "58") (name "TIP") (class "Default")
      (node (ref "J8") (pin "P1") (pinfunction "1_P1") (pintype "passive"))
      (node (ref "MS1") (pin "9") (pinfunction "GPIOA4_9") (pintype "bidirectional"))
      (node (ref "R14") (pin "2") (pinfunction "2_2") (pintype "passive"))
      (node (ref "TP8") (pin "1") (pinfunction "P$1_1") (pintype "bidirectional"))
    )
    (net (code "59") (name "TX") (class "Default")
      (node (ref "J10") (pin "2") (pinfunction "2_2") (pintype "passive"))
      (node (ref "MS1") (pin "15") (pinfunction "GPIOTX_15") (pintype "bidirectional"))
    )
    (net (code "60") (name "VBAT-") (class "Default")
      (node (ref "J6") (pin "2") (pinfunction "2_2") (pintype "passive"))
      (node (ref "Q1") (pin "3") (pinfunction "D_3") (pintype "bidirectional"))
    )
    (net (code "61") (name "VBAT_FEATHER") (class "Default")
      (node (ref "J6") (pin "1") (pinfunction "1_1") (pintype "passive"))
      (node (ref "J9") (pin "1") (pinfunction "BAT_1") (pintype "power_in"))
      (node (ref "MS1") (pin "28") (pinfunction "VBAT_28") (pintype "power_in"))
      (node (ref "Q1") (pin "1") (pinfunction "G_1") (pintype "bidirectional"))
    )
    (net (code "62") (name "VBUS_FEATHER") (class "Default")
      (node (ref "J7") (pin "1") (pinfunction "1_1") (pintype "passive"))
      (node (ref "MS1") (pin "26") (pinfunction "USB_26") (pintype "power_in"))
      (node (ref "Q2") (pin "1") (pinfunction "G_1") (pintype "bidirectional"))
    )
    (net (code "63") (name "VSYS-") (class "Default")
      (node (ref "J7") (pin "2") (pinfunction "2_2") (pintype "passive"))
      (node (ref "Q2") (pin "3") (pinfunction "D_3") (pintype "bidirectional"))
    )
    (net (code "64") (name "WAKE") (class "Default")
      (node (ref "U2") (pin "5") (pinfunction "WAKE_5") (pintype "output"))
      (node (ref "U3") (pin "17") (pinfunction "GP5_17") (pintype "bidirectional"))
    )
    (net (code "65") (name "WD_HOLD") (class "Default")
      (node (ref "U2") (pin "4") (pinfunction "DONE_4") (pintype "input"))
      (node (ref "U3") (pin "18") (pinfunction "GP6_18") (pintype "bidirectional"))
    )
    (net (code "66") (name "unconnected-(MS1-AREF-Pad3)") (class "Default")
      (node (ref "MS1") (pin "3") (pinfunction "AREF_3") (pintype "passive"))
    )
    (net (code "67") (name "unconnected-(MS1-EN-Pad27)") (class "Default")
      (node (ref "MS1") (pin "27") (pinfunction "EN_27") (pintype "passive"))
    )
    (net (code "68") (name "unconnected-(MS1-NC-Pad16)") (class "Default")
      (node (ref "MS1") (pin "16") (pinfunction "NC_16") (pintype "passive"))
    )
    (net (code "69") (name "unconnected-(SD1-DAT1-Pad8)") (class "Default")
      (node (ref "SD1") (pin "8") (pinfunction "DAT1_8") (pintype "bidirectional"))
    )
    (net (code "70") (name "unconnected-(SD1-DAT2-Pad1)") (class "Default")
      (node (ref "SD1") (pin "1") (pinfunction "DAT2_1") (pintype "bidirectional"))
    )
    (net (code "71") (name "unconnected-(U6-WAKE-Pad5)") (class "Default")
      (node (ref "U6") (pin "5") (pinfunction "WAKE_5") (pintype "output"))
    )
  )
)
